# SimpleExt.net
KiCad netlist of a schematic drawn in EAGLE
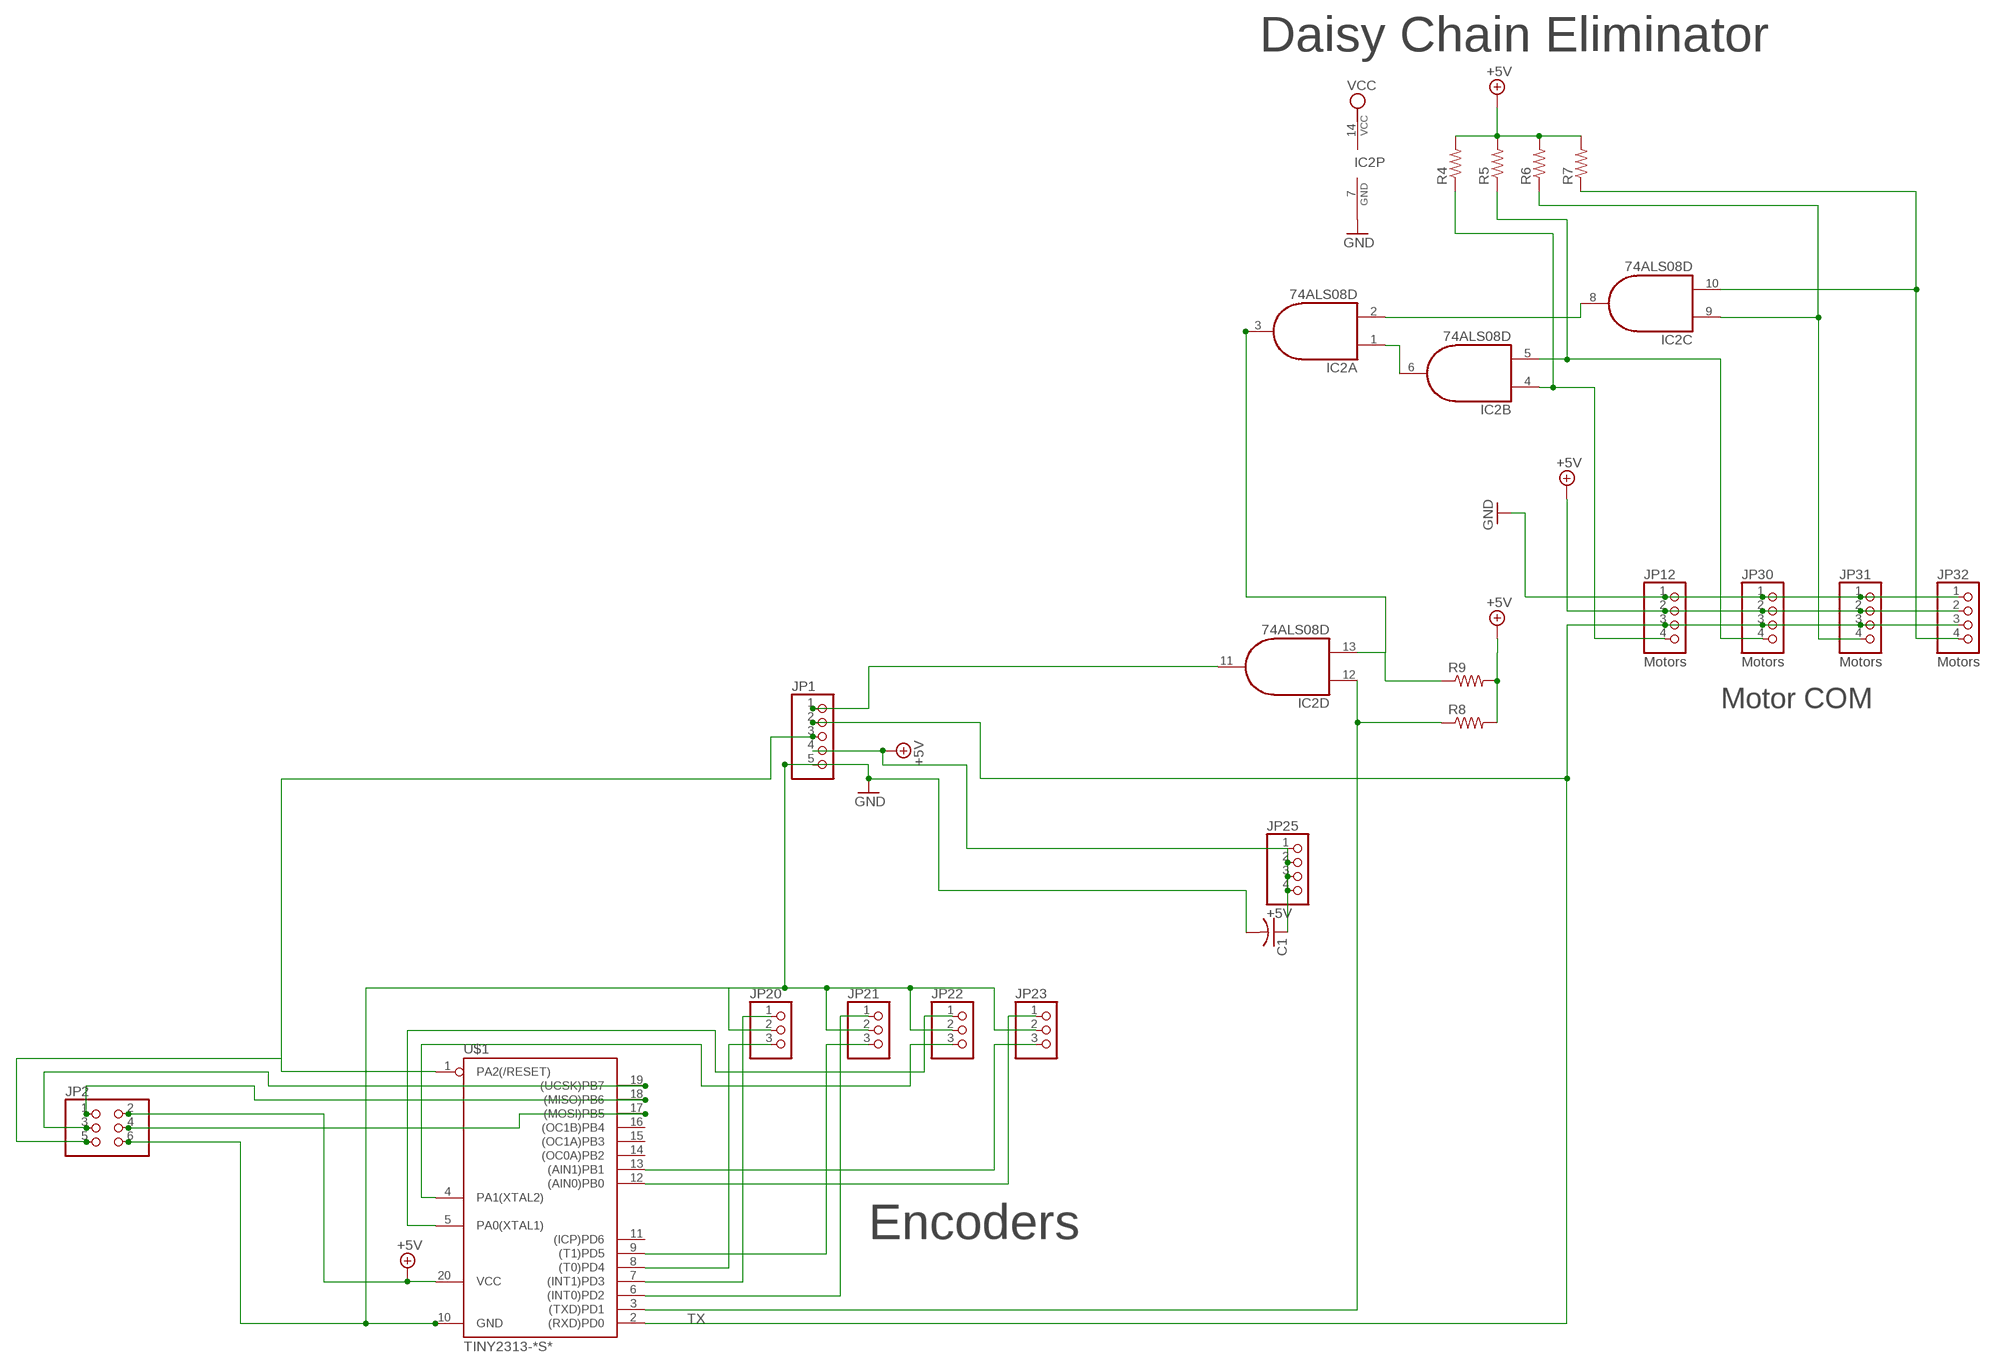
[diagram p0: schematic, sheet 1]

(export (version "E")
  (design (tool "Eeschema 10.0.6"))
  (components
    (comp (ref "C1")
      (value "C-USC0603K")
      (footprint "eagle-import:C0603K")
      (libsource (lib "eagle-import") (part "C-USC0603K"))
    )
    (comp (ref "IC2")
      (value "74ALS08D")
      (footprint "eagle-import:SO14")
      (libsource (lib "eagle-import") (part "7408DALS"))
    )
    (comp (ref "JP1")
      (value "PINHD-1X5")
      (footprint "eagle-import:1X05")
      (libsource (lib "eagle-import") (part "PINHD-1X5"))
    )
    (comp (ref "JP2")
      (value "PINHD-2X3")
      (footprint "eagle-import:2X03")
      (libsource (lib "eagle-import") (part "PINHD-2X3"))
    )
    (comp (ref "JP12")
      (value "Motors")
      (footprint "eagle-import:1X04-S")
      (libsource (lib "eagle-import") (part "PINHD-1X04_2.54-S"))
    )
    (comp (ref "JP20")
      (value "PINHD-1X03_2.54-S")
      (footprint "eagle-import:1X03-S")
      (libsource (lib "eagle-import") (part "PINHD-1X03_2.54-S"))
    )
    (comp (ref "JP21")
      (value "PINHD-1X03_2.54-S")
      (footprint "eagle-import:1X03-S")
      (libsource (lib "eagle-import") (part "PINHD-1X03_2.54-S"))
    )
    (comp (ref "JP22")
      (value "PINHD-1X03_2.54-S")
      (footprint "eagle-import:1X03-S")
      (libsource (lib "eagle-import") (part "PINHD-1X03_2.54-S"))
    )
    (comp (ref "JP23")
      (value "PINHD-1X03_2.54-S")
      (footprint "eagle-import:1X03-S")
      (libsource (lib "eagle-import") (part "PINHD-1X03_2.54-S"))
    )
    (comp (ref "JP25")
      (value "+5V")
      (footprint "eagle-import:1X04-S")
      (libsource (lib "eagle-import") (part "PINHD-1X04_2.54-S"))
    )
    (comp (ref "JP30")
      (value "Motors")
      (footprint "eagle-import:1X04-S")
      (libsource (lib "eagle-import") (part "PINHD-1X04_2.54-S"))
    )
    (comp (ref "JP31")
      (value "Motors")
      (footprint "eagle-import:1X04-S")
      (libsource (lib "eagle-import") (part "PINHD-1X04_2.54-S"))
    )
    (comp (ref "JP32")
      (value "Motors")
      (footprint "eagle-import:1X04-S")
      (libsource (lib "eagle-import") (part "PINHD-1X04_2.54-S"))
    )
    (comp (ref "R4")
      (value "R-US_R0603")
      (footprint "eagle-import:R0603")
      (libsource (lib "eagle-import") (part "R-US_R0603"))
    )
    (comp (ref "R5")
      (value "R-US_R0603")
      (footprint "eagle-import:R0603")
      (libsource (lib "eagle-import") (part "R-US_R0603"))
    )
    (comp (ref "R6")
      (value "R-US_R0603")
      (footprint "eagle-import:R0603")
      (libsource (lib "eagle-import") (part "R-US_R0603"))
    )
    (comp (ref "R7")
      (value "R-US_R0603")
      (footprint "eagle-import:R0603")
      (libsource (lib "eagle-import") (part "R-US_R0603"))
    )
    (comp (ref "R8")
      (value "R-US_R0603")
      (footprint "eagle-import:R0603")
      (libsource (lib "eagle-import") (part "R-US_R0603"))
    )
    (comp (ref "R9")
      (value "R-US_R0603")
      (footprint "eagle-import:R0603")
      (libsource (lib "eagle-import") (part "R-US_R0603"))
    )
    (comp (ref "U$1")
      (value "TINY2313-*S*")
      (footprint "eagle-import:SO20L$")
      (libsource (lib "eagle-import") (part "TINY2313-S"))
    )
  )
  (nets
    (net (code "1") (name "+5V") (class "Default")
      (node (ref "C1") (pin "1") (pinfunction "1_1") (pintype "passive"))
      (node (ref "JP1") (pin "4") (pinfunction "4_4") (pintype "passive"))
      (node (ref "JP12") (pin "2") (pinfunction "2_2") (pintype "passive"))
      (node (ref "JP2") (pin "2") (pinfunction "2_2") (pintype "passive"))
      (node (ref "JP25") (pin "1") (pinfunction "1_1") (pintype "passive"))
      (node (ref "JP25") (pin "2") (pinfunction "2_2") (pintype "passive"))
      (node (ref "JP25") (pin "3") (pinfunction "3_3") (pintype "passive"))
      (node (ref "JP25") (pin "4") (pinfunction "4_4") (pintype "passive"))
      (node (ref "JP30") (pin "2") (pinfunction "2_2") (pintype "passive"))
      (node (ref "JP31") (pin "2") (pinfunction "2_2") (pintype "passive"))
      (node (ref "JP32") (pin "2") (pinfunction "2_2") (pintype "passive"))
      (node (ref "R4") (pin "2") (pinfunction "2_2") (pintype "passive"))
      (node (ref "R5") (pin "2") (pinfunction "2_2") (pintype "passive"))
      (node (ref "R6") (pin "2") (pinfunction "2_2") (pintype "passive"))
      (node (ref "R7") (pin "2") (pinfunction "2_2") (pintype "passive"))
      (node (ref "R8") (pin "2") (pinfunction "2_2") (pintype "passive"))
      (node (ref "R9") (pin "2") (pinfunction "2_2") (pintype "passive"))
      (node (ref "U$1") (pin "20") (pinfunction "VCC_20") (pintype "power_in"))
    )
    (net (code "2") (name "/TX") (class "Default")
      (node (ref "JP1") (pin "2") (pinfunction "2_2") (pintype "passive"))
      (node (ref "JP12") (pin "3") (pinfunction "3_3") (pintype "passive"))
      (node (ref "JP30") (pin "3") (pinfunction "3_3") (pintype "passive"))
      (node (ref "JP31") (pin "3") (pinfunction "3_3") (pintype "passive"))
      (node (ref "JP32") (pin "3") (pinfunction "3_3") (pintype "passive"))
      (node (ref "U$1") (pin "2") (pinfunction "(RXD)PD0_2") (pintype "bidirectional"))
    )
    (net (code "3") (name "GND") (class "Default")
      (node (ref "C1") (pin "2") (pinfunction "2_2") (pintype "passive"))
      (node (ref "IC2") (pin "7") (pinfunction "GND_7") (pintype "power_in"))
      (node (ref "JP1") (pin "5") (pinfunction "5_5") (pintype "passive"))
      (node (ref "JP12") (pin "1") (pinfunction "1_1") (pintype "passive"))
      (node (ref "JP2") (pin "6") (pinfunction "6_6") (pintype "passive"))
      (node (ref "JP20") (pin "2") (pinfunction "2_2") (pintype "passive"))
      (node (ref "JP21") (pin "2") (pinfunction "2_2") (pintype "passive"))
      (node (ref "JP22") (pin "2") (pinfunction "2_2") (pintype "passive"))
      (node (ref "JP23") (pin "2") (pinfunction "2_2") (pintype "passive"))
      (node (ref "JP30") (pin "1") (pinfunction "1_1") (pintype "passive"))
      (node (ref "JP31") (pin "1") (pinfunction "1_1") (pintype "passive"))
      (node (ref "JP32") (pin "1") (pinfunction "1_1") (pintype "passive"))
      (node (ref "U$1") (pin "10") (pinfunction "GND_10") (pintype "power_in"))
    )
    (net (code "4") (name "Net-(IC2A-I0)") (class "Default")
      (node (ref "IC2") (pin "1") (pinfunction "I0_1") (pintype "input"))
      (node (ref "IC2") (pin "6") (pinfunction "O_6") (pintype "output"))
    )
    (net (code "5") (name "Net-(IC2A-I1)") (class "Default")
      (node (ref "IC2") (pin "2") (pinfunction "I1_2") (pintype "input"))
      (node (ref "IC2") (pin "8") (pinfunction "O_8") (pintype "output"))
    )
    (net (code "6") (name "Net-(IC2A-O)") (class "Default")
      (node (ref "IC2") (pin "13") (pinfunction "I1_13") (pintype "input"))
      (node (ref "IC2") (pin "3") (pinfunction "O_3") (pintype "output"))
      (node (ref "R9") (pin "1") (pinfunction "1_1") (pintype "passive"))
    )
    (net (code "7") (name "Net-(IC2B-I0)") (class "Default")
      (node (ref "IC2") (pin "4") (pinfunction "I0_4") (pintype "input"))
      (node (ref "JP12") (pin "4") (pinfunction "4_4") (pintype "passive"))
      (node (ref "R4") (pin "1") (pinfunction "1_1") (pintype "passive"))
    )
    (net (code "8") (name "Net-(IC2B-I1)") (class "Default")
      (node (ref "IC2") (pin "5") (pinfunction "I1_5") (pintype "input"))
      (node (ref "JP30") (pin "4") (pinfunction "4_4") (pintype "passive"))
      (node (ref "R5") (pin "1") (pinfunction "1_1") (pintype "passive"))
    )
    (net (code "9") (name "Net-(IC2C-I0)") (class "Default")
      (node (ref "IC2") (pin "9") (pinfunction "I0_9") (pintype "input"))
      (node (ref "JP31") (pin "4") (pinfunction "4_4") (pintype "passive"))
      (node (ref "R6") (pin "1") (pinfunction "1_1") (pintype "passive"))
    )
    (net (code "10") (name "Net-(IC2C-I1)") (class "Default")
      (node (ref "IC2") (pin "10") (pinfunction "I1_10") (pintype "input"))
      (node (ref "JP32") (pin "4") (pinfunction "4_4") (pintype "passive"))
      (node (ref "R7") (pin "1") (pinfunction "1_1") (pintype "passive"))
    )
    (net (code "11") (name "Net-(IC2D-I0)") (class "Default")
      (node (ref "IC2") (pin "12") (pinfunction "I0_12") (pintype "input"))
      (node (ref "R8") (pin "1") (pinfunction "1_1") (pintype "passive"))
      (node (ref "U$1") (pin "3") (pinfunction "(TXD)PD1_3") (pintype "bidirectional"))
    )
    (net (code "12") (name "Net-(IC2D-O)") (class "Default")
      (node (ref "IC2") (pin "11") (pinfunction "O_11") (pintype "output"))
      (node (ref "JP1") (pin "1") (pinfunction "1_1") (pintype "passive"))
    )
    (net (code "13") (name "Net-(U$1-(AIN0)PB0)") (class "Default")
      (node (ref "JP23") (pin "1") (pinfunction "1_1") (pintype "passive"))
      (node (ref "U$1") (pin "12") (pinfunction "(AIN0)PB0_12") (pintype "bidirectional"))
    )
    (net (code "14") (name "Net-(U$1-(AIN1)PB1)") (class "Default")
      (node (ref "JP23") (pin "3") (pinfunction "3_3") (pintype "passive"))
      (node (ref "U$1") (pin "13") (pinfunction "(AIN1)PB1_13") (pintype "bidirectional"))
    )
    (net (code "15") (name "Net-(U$1-(INT0)PD2)") (class "Default")
      (node (ref "JP21") (pin "1") (pinfunction "1_1") (pintype "passive"))
      (node (ref "U$1") (pin "6") (pinfunction "(INT0)PD2_6") (pintype "bidirectional"))
    )
    (net (code "16") (name "Net-(U$1-(INT1)PD3)") (class "Default")
      (node (ref "JP20") (pin "1") (pinfunction "1_1") (pintype "passive"))
      (node (ref "U$1") (pin "7") (pinfunction "(INT1)PD3_7") (pintype "bidirectional"))
    )
    (net (code "17") (name "Net-(U$1-(MISO)PB6)") (class "Default")
      (node (ref "JP2") (pin "1") (pinfunction "1_1") (pintype "passive"))
      (node (ref "U$1") (pin "18") (pinfunction "(MISO)PB6_18") (pintype "bidirectional"))
    )
    (net (code "18") (name "Net-(U$1-(MOSI)PB5)") (class "Default")
      (node (ref "JP2") (pin "4") (pinfunction "4_4") (pintype "passive"))
      (node (ref "U$1") (pin "17") (pinfunction "(MOSI)PB5_17") (pintype "bidirectional"))
    )
    (net (code "19") (name "Net-(U$1-(T0)PD4)") (class "Default")
      (node (ref "JP20") (pin "3") (pinfunction "3_3") (pintype "passive"))
      (node (ref "U$1") (pin "8") (pinfunction "(T0)PD4_8") (pintype "bidirectional"))
    )
    (net (code "20") (name "Net-(U$1-(T1)PD5)") (class "Default")
      (node (ref "JP21") (pin "3") (pinfunction "3_3") (pintype "passive"))
      (node (ref "U$1") (pin "9") (pinfunction "(T1)PD5_9") (pintype "bidirectional"))
    )
    (net (code "21") (name "Net-(U$1-(UCSK)PB7)") (class "Default")
      (node (ref "JP2") (pin "3") (pinfunction "3_3") (pintype "passive"))
      (node (ref "U$1") (pin "19") (pinfunction "(UCSK)PB7_19") (pintype "bidirectional"))
    )
    (net (code "22") (name "Net-(U$1-PA0(XTAL1))") (class "Default")
      (node (ref "JP22") (pin "1") (pinfunction "1_1") (pintype "passive"))
      (node (ref "U$1") (pin "5") (pinfunction "PA0(XTAL1)_5") (pintype "bidirectional"))
    )
    (net (code "23") (name "Net-(U$1-PA1(XTAL2))") (class "Default")
      (node (ref "JP22") (pin "3") (pinfunction "3_3") (pintype "passive"))
      (node (ref "U$1") (pin "4") (pinfunction "PA1(XTAL2)_4") (pintype "bidirectional"))
    )
    (net (code "24") (name "Net-(U$1-PA2({slash}RESET))") (class "Default")
      (node (ref "JP1") (pin "3") (pinfunction "3_3") (pintype "passive"))
      (node (ref "JP2") (pin "5") (pinfunction "5_5") (pintype "passive"))
      (node (ref "U$1") (pin "1") (pinfunction "PA2(/RESET)_1") (pintype "input"))
    )
    (net (code "25") (name "VCC") (class "Default")
      (node (ref "IC2") (pin "14") (pinfunction "VCC_14") (pintype "power_in"))
    )
    (net (code "26") (name "unconnected-(U$1-(ICP)PD6-Pad11)") (class "Default")
      (node (ref "U$1") (pin "11") (pinfunction "(ICP)PD6_11") (pintype "bidirectional"))
    )
    (net (code "27") (name "unconnected-(U$1-(OC0A)PB2-Pad14)") (class "Default")
      (node (ref "U$1") (pin "14") (pinfunction "(OC0A)PB2_14") (pintype "bidirectional"))
    )
    (net (code "28") (name "unconnected-(U$1-(OC1A)PB3-Pad15)") (class "Default")
      (node (ref "U$1") (pin "15") (pinfunction "(OC1A)PB3_15") (pintype "bidirectional"))
    )
    (net (code "29") (name "unconnected-(U$1-(OC1B)PB4-Pad16)") (class "Default")
      (node (ref "U$1") (pin "16") (pinfunction "(OC1B)PB4_16") (pintype "bidirectional"))
    )
  )
)
